# CPU.net
KiCad netlist of a schematic drawn in Altium Designer
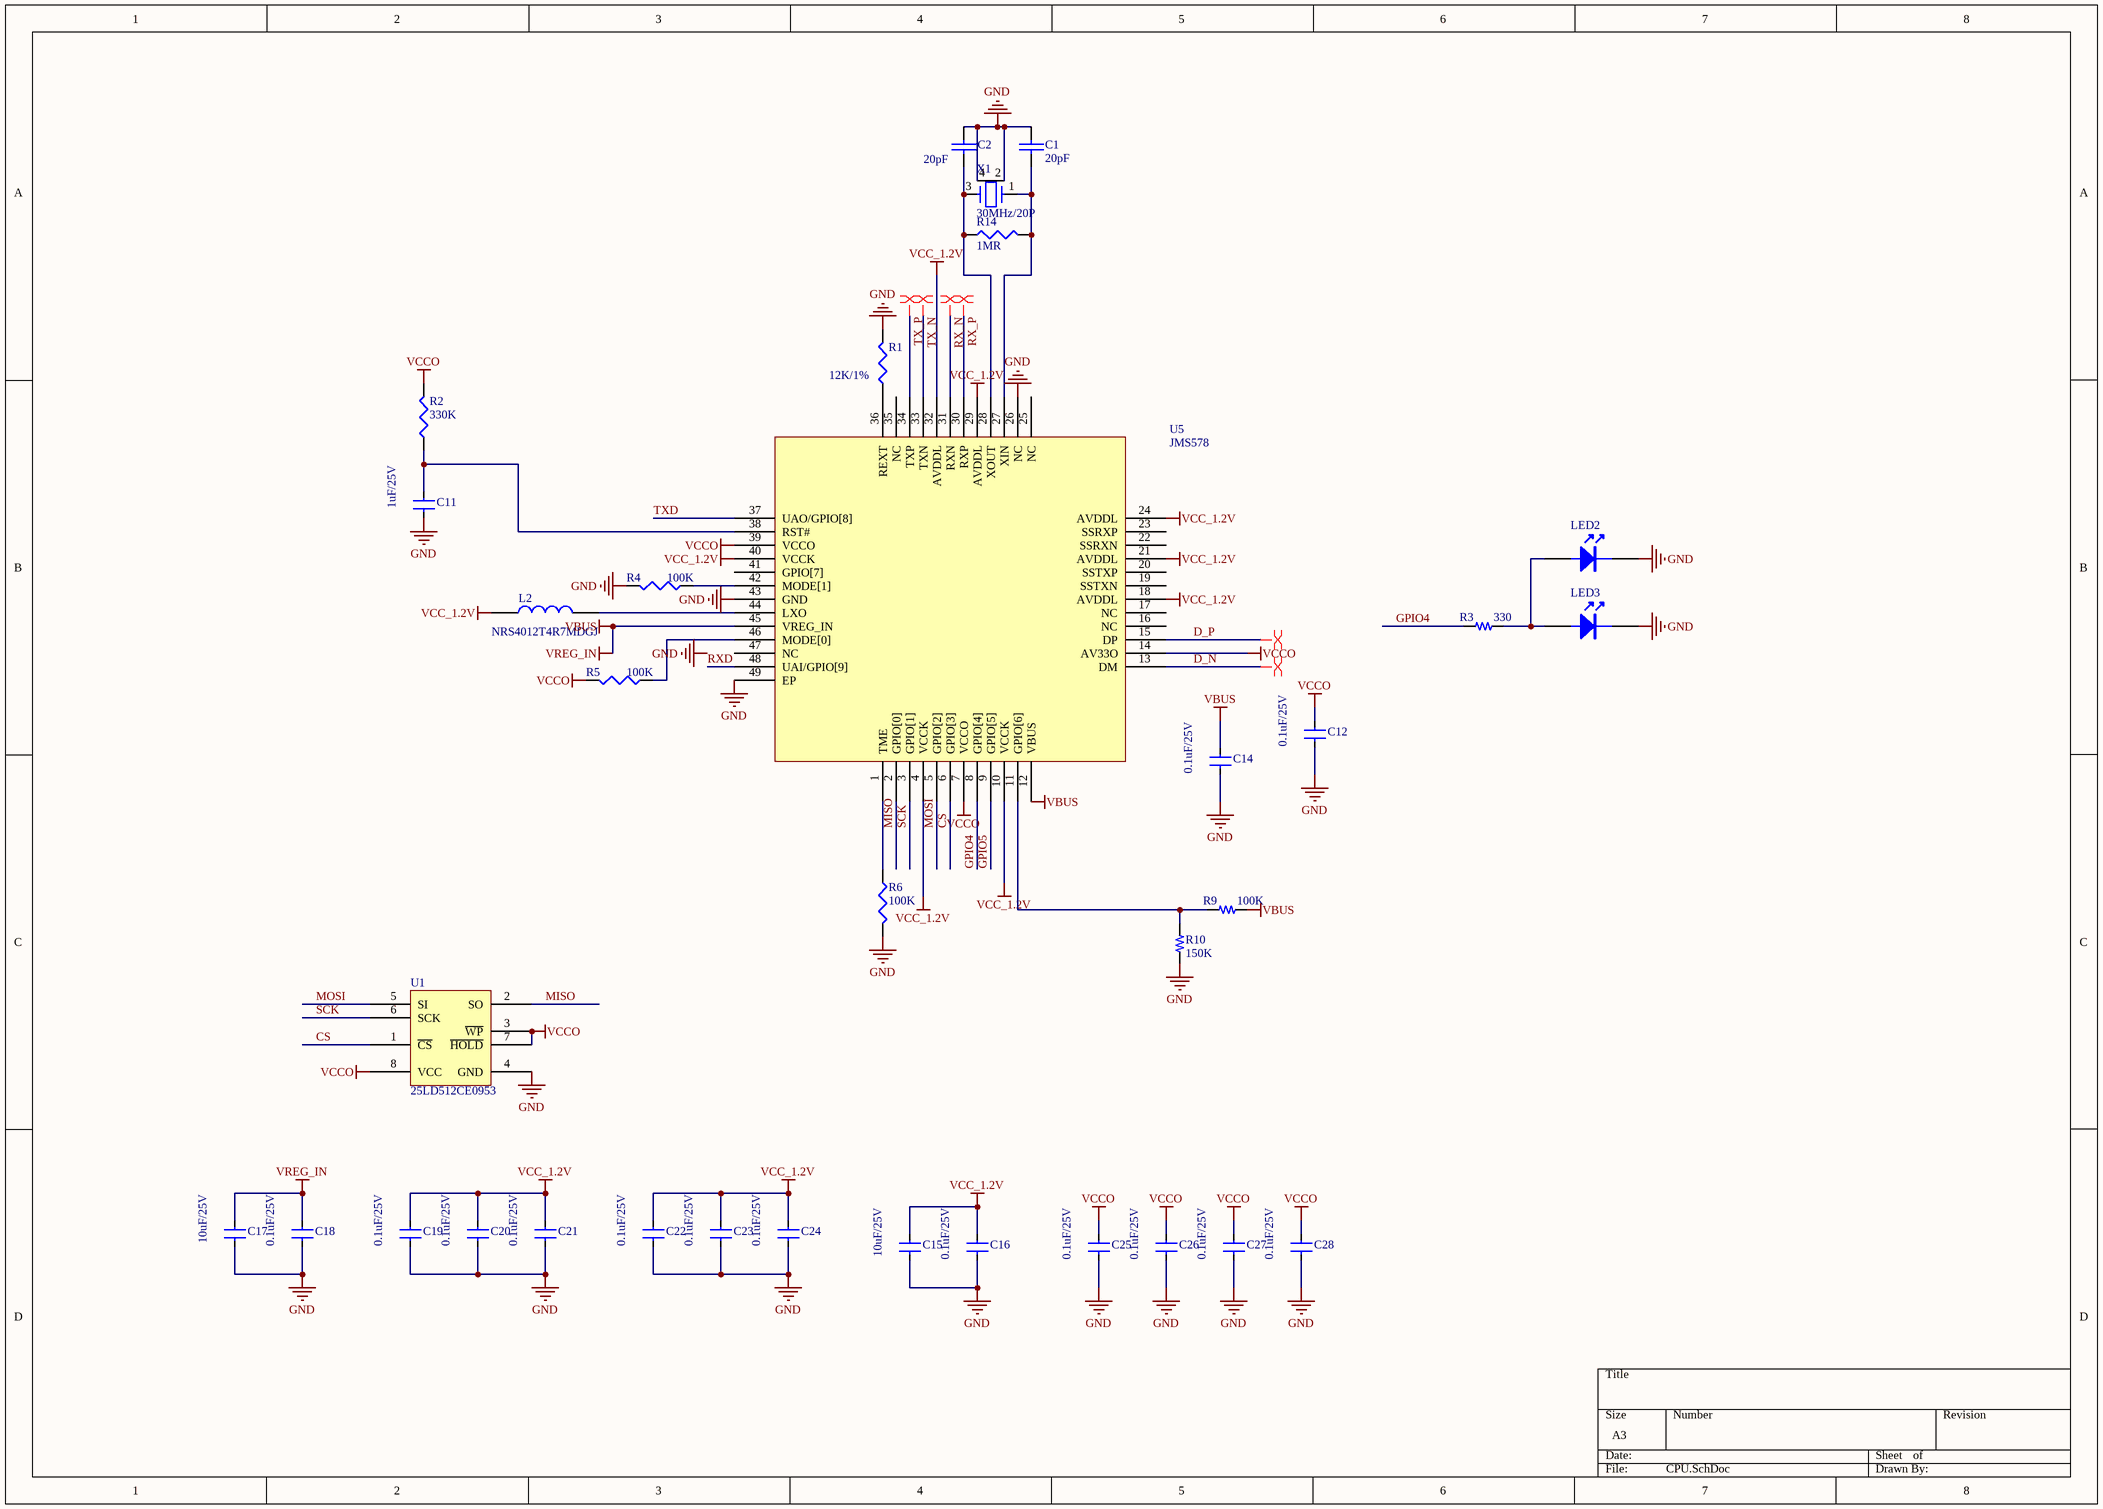
[diagram p0: CPU.SchDoc]

(export (version "E")
  (design (tool "Eeschema 10.0.6"))
  (components
    (comp (ref "C1")
      (value "20pF")
      (footprint "0603c")
      (description "Capacitor")
      (libsource (lib "SM") (part "CAP"))
    )
    (comp (ref "C2")
      (value "20pF")
      (footprint "0603C")
      (description "Capacitor")
      (libsource (lib "SM") (part "CAP"))
    )
    (comp (ref "C11")
      (value "1uF/25V")
      (footprint "0603C")
      (description "CCX85-103")
      (libsource (lib "无极性电容") (part "0.01UF"))
    )
    (comp (ref "C12")
      (value "0.1uF/25V")
      (footprint "0603C")
      (description "CCX85-103")
      (libsource (lib "无极性电容") (part "0.01UF"))
    )
    (comp (ref "C14")
      (value "0.1uF/25V")
      (footprint "0603C")
      (description "CCX85-103")
      (libsource (lib "无极性电容") (part "0.01UF"))
    )
    (comp (ref "C15")
      (value "10uF/25V")
      (footprint "0603C")
      (description "CCX85-103")
      (libsource (lib "无极性电容") (part "0.01UF"))
    )
    (comp (ref "C16")
      (value "0.1uF/25V")
      (footprint "0603C")
      (description "CCX85-103")
      (libsource (lib "无极性电容") (part "0.01UF"))
    )
    (comp (ref "C17")
      (value "10uF/25V")
      (footprint "0603C")
      (description "CCX85-103")
      (libsource (lib "无极性电容") (part "0.01UF"))
    )
    (comp (ref "C18")
      (value "0.1uF/25V")
      (footprint "0603C")
      (description "CCX85-103")
      (libsource (lib "无极性电容") (part "0.01UF"))
    )
    (comp (ref "C19")
      (value "0.1uF/25V")
      (footprint "0603C")
      (description "CCX85-103")
      (libsource (lib "无极性电容") (part "0.01UF"))
    )
    (comp (ref "C20")
      (value "0.1uF/25V")
      (footprint "0603C")
      (description "CCX85-103")
      (libsource (lib "无极性电容") (part "0.01UF"))
    )
    (comp (ref "C21")
      (value "0.1uF/25V")
      (footprint "0603C")
      (description "CCX85-103")
      (libsource (lib "无极性电容") (part "0.01UF"))
    )
    (comp (ref "C22")
      (value "0.1uF/25V")
      (footprint "0603C")
      (description "CCX85-103")
      (libsource (lib "无极性电容") (part "0.01UF"))
    )
    (comp (ref "C23")
      (value "0.1uF/25V")
      (footprint "0603C")
      (description "CCX85-103")
      (libsource (lib "无极性电容") (part "0.01UF"))
    )
    (comp (ref "C24")
      (value "0.1uF/25V")
      (footprint "0603C")
      (description "CCX85-103")
      (libsource (lib "无极性电容") (part "0.01UF"))
    )
    (comp (ref "C25")
      (value "0.1uF/25V")
      (footprint "0603C")
      (description "CCX85-103")
      (libsource (lib "无极性电容") (part "0.01UF"))
    )
    (comp (ref "C26")
      (value "0.1uF/25V")
      (footprint "0603C")
      (description "CCX85-103")
      (libsource (lib "无极性电容") (part "0.01UF"))
    )
    (comp (ref "C27")
      (value "0.1uF/25V")
      (footprint "0603C")
      (description "CCX85-103")
      (libsource (lib "无极性电容") (part "0.01UF"))
    )
    (comp (ref "C28")
      (value "0.1uF/25V")
      (footprint "0603C")
      (description "CCX85-103")
      (libsource (lib "无极性电容") (part "0.01UF"))
    )
    (comp (ref "L2")
      (value "NRS4012T4R7MDGJ")
      (footprint "NRS4012T4R7MDGJ")
      (libsource (lib "*") (part "INDUCTOR"))
    )
    (comp (ref "LED2") (value "~") (footprint "0603LED") (libsource (lib "*") (part "LED")))
    (comp (ref "LED3") (value "~") (footprint "0603LED") (libsource (lib "*") (part "LED")))
    (comp (ref "R1")
      (value "12K/1%")
      (footprint "0603R")
      (description "Resistor")
      (fields (field (name "PUBLISHER") "Altium Limited"))
      (libsource (lib "SM") (part "Res3"))
    )
    (comp (ref "R2")
      (value "330K")
      (footprint "0603R")
      (description "Resistor")
      (fields (field (name "PUBLISHER") "Altium Limited"))
      (libsource (lib "SM") (part "Res3"))
    )
    (comp (ref "R3") (value "330") (footprint "0603R") (description "R") (libsource (lib "JRJ_1") (part "R")))
    (comp (ref "R4")
      (value "100K")
      (footprint "0603R")
      (description "Resistor")
      (fields (field (name "PUBLISHER") "Altium Limited"))
      (libsource (lib "SM") (part "Res3"))
    )
    (comp (ref "R5")
      (value "100K")
      (footprint "0603R")
      (description "Resistor")
      (fields (field (name "PUBLISHER") "Altium Limited"))
      (libsource (lib "SM") (part "Res3"))
    )
    (comp (ref "R6")
      (value "100K")
      (footprint "0603R")
      (description "Resistor")
      (fields (field (name "PUBLISHER") "Altium Limited"))
      (libsource (lib "SM") (part "Res3"))
    )
    (comp (ref "R9")
      (value "100K")
      (footprint "0603R")
      (description "R")
      (libsource (lib "JRJ_1") (part "R"))
    )
    (comp (ref "R10")
      (value "150K")
      (footprint "0603R")
      (description "R")
      (libsource (lib "JRJ_1") (part "R"))
    )
    (comp (ref "R14")
      (value "1MR")
      (footprint "0603R")
      (description "Resistor")
      (fields (field (name "PUBLISHER") "Altium Limited"))
      (libsource (lib "SM") (part "Res3"))
    )
    (comp (ref "U1")
      (value "25LD512CE0953")
      (footprint "SO-8")
      (libsource (lib "Schlib_20110825") (part "M25P40-VMN6"))
    )
    (comp (ref "U5") (value "JMS578") (footprint "QFN400P600-8N") (libsource (lib "stm32") (part "JMS578")))
    (comp (ref "X1")
      (value "30MHz/20P")
      (footprint "XTAL4TN_3225")
      (libsource (lib "JRJ") (part "CRYSTAL_2"))
    )
  )
  (nets
    (net (code "1") (name "/CS") (class "Default")
      (node (ref "U1") (pin "1") (pinfunction "~{CS}_1") (pintype "passive"))
      (node (ref "U5") (pin "6") (pinfunction "GPIO[3]_6") (pintype "passive"))
    )
    (net (code "2") (name "/D_N") (class "Default")
      (node (ref "U5") (pin "13") (pinfunction "DM_13") (pintype "passive"))
    )
    (net (code "3") (name "/D_P") (class "Default")
      (node (ref "U5") (pin "15") (pinfunction "DP_15") (pintype "passive"))
    )
    (net (code "4") (name "/GPIO4") (class "Default")
      (node (ref "R3") (pin "1") (pintype "passive"))
      (node (ref "U5") (pin "8") (pinfunction "GPIO[4]_8") (pintype "passive"))
    )
    (net (code "5") (name "/GPIO5") (class "Default")
      (node (ref "U5") (pin "9") (pinfunction "GPIO[5]_9") (pintype "passive"))
    )
    (net (code "6") (name "/MISO") (class "Default")
      (node (ref "U1") (pin "2") (pinfunction "SO_2") (pintype "passive"))
      (node (ref "U5") (pin "2") (pinfunction "GPIO[0]_2") (pintype "passive"))
    )
    (net (code "7") (name "/MOSI") (class "Default")
      (node (ref "U1") (pin "5") (pinfunction "SI_5") (pintype "passive"))
      (node (ref "U5") (pin "5") (pinfunction "GPIO[2]_5") (pintype "passive"))
    )
    (net (code "8") (name "/RXD") (class "Default")
      (node (ref "U5") (pin "48") (pinfunction "UAI/GPIO[9]_48") (pintype "passive"))
    )
    (net (code "9") (name "/RX_N") (class "Default")
      (node (ref "U5") (pin "31") (pinfunction "RXN_31") (pintype "passive"))
    )
    (net (code "10") (name "/RX_P") (class "Default")
      (node (ref "U5") (pin "30") (pinfunction "RXP_30") (pintype "passive"))
    )
    (net (code "11") (name "/SCK") (class "Default")
      (node (ref "U1") (pin "6") (pinfunction "SCK_6") (pintype "passive"))
      (node (ref "U5") (pin "3") (pinfunction "GPIO[1]_3") (pintype "passive"))
    )
    (net (code "12") (name "/TXD") (class "Default")
      (node (ref "U5") (pin "37") (pinfunction "UAO/GPIO[8]_37") (pintype "passive"))
    )
    (net (code "13") (name "/TX_N") (class "Default")
      (node (ref "U5") (pin "33") (pinfunction "TXN_33") (pintype "passive"))
    )
    (net (code "14") (name "/TX_P") (class "Default")
      (node (ref "U5") (pin "34") (pinfunction "TXP_34") (pintype "passive"))
    )
    (net (code "15") (name "GND") (class "Default")
      (node (ref "C1") (pin "1") (pinfunction "1_1") (pintype "passive"))
      (node (ref "C11") (pin "2") (pinfunction "2_2") (pintype "passive"))
      (node (ref "C12") (pin "2") (pinfunction "2_2") (pintype "passive"))
      (node (ref "C14") (pin "2") (pinfunction "2_2") (pintype "passive"))
      (node (ref "C15") (pin "2") (pinfunction "2_2") (pintype "passive"))
      (node (ref "C16") (pin "2") (pinfunction "2_2") (pintype "passive"))
      (node (ref "C17") (pin "2") (pinfunction "2_2") (pintype "passive"))
      (node (ref "C18") (pin "2") (pinfunction "2_2") (pintype "passive"))
      (node (ref "C19") (pin "2") (pinfunction "2_2") (pintype "passive"))
      (node (ref "C2") (pin "1") (pinfunction "1_1") (pintype "passive"))
      (node (ref "C20") (pin "2") (pinfunction "2_2") (pintype "passive"))
      (node (ref "C21") (pin "2") (pinfunction "2_2") (pintype "passive"))
      (node (ref "C22") (pin "2") (pinfunction "2_2") (pintype "passive"))
      (node (ref "C23") (pin "2") (pinfunction "2_2") (pintype "passive"))
      (node (ref "C24") (pin "2") (pinfunction "2_2") (pintype "passive"))
      (node (ref "C25") (pin "2") (pinfunction "2_2") (pintype "passive"))
      (node (ref "C26") (pin "2") (pinfunction "2_2") (pintype "passive"))
      (node (ref "C27") (pin "2") (pinfunction "2_2") (pintype "passive"))
      (node (ref "C28") (pin "2") (pinfunction "2_2") (pintype "passive"))
      (node (ref "LED2") (pin "2") (pinfunction "2_2") (pintype "passive"))
      (node (ref "LED3") (pin "2") (pinfunction "2_2") (pintype "passive"))
      (node (ref "R1") (pin "2") (pinfunction "2_2") (pintype "passive"))
      (node (ref "R10") (pin "1") (pintype "passive"))
      (node (ref "R4") (pin "2") (pinfunction "2_2") (pintype "passive"))
      (node (ref "R6") (pin "2") (pinfunction "2_2") (pintype "passive"))
      (node (ref "U1") (pin "4") (pinfunction "GND_4") (pintype "passive"))
      (node (ref "U5") (pin "26") (pinfunction "NC_26") (pintype "passive"))
      (node (ref "U5") (pin "43") (pinfunction "GND_43") (pintype "passive"))
      (node (ref "U5") (pin "49") (pinfunction "EP_49") (pintype "passive"))
      (node (ref "X1") (pin "2") (pinfunction "GND_2") (pintype "passive"))
      (node (ref "X1") (pin "4") (pinfunction "GND_4") (pintype "passive"))
    )
    (net (code "16") (name "Net-(LED2-Pad1)") (class "Default")
      (node (ref "LED2") (pin "1") (pinfunction "1_1") (pintype "passive"))
      (node (ref "LED3") (pin "1") (pinfunction "1_1") (pintype "passive"))
      (node (ref "R3") (pin "2") (pintype "passive"))
    )
    (net (code "17") (name "Net-(U5-GPIO[6])") (class "Default")
      (node (ref "R10") (pin "2") (pintype "passive"))
      (node (ref "R9") (pin "1") (pintype "passive"))
      (node (ref "U5") (pin "11") (pinfunction "GPIO[6]_11") (pintype "passive"))
    )
    (net (code "18") (name "Net-(U5-LXO)") (class "Default")
      (node (ref "L2") (pin "2") (pinfunction "2_2") (pintype "passive"))
      (node (ref "U5") (pin "44") (pinfunction "LXO_44") (pintype "passive"))
    )
    (net (code "19") (name "Net-(U5-MODE[0])") (class "Default")
      (node (ref "R5") (pin "1") (pinfunction "1_1") (pintype "passive"))
      (node (ref "U5") (pin "46") (pinfunction "MODE[0]_46") (pintype "passive"))
    )
    (net (code "20") (name "Net-(U5-MODE[1])") (class "Default")
      (node (ref "R4") (pin "1") (pinfunction "1_1") (pintype "passive"))
      (node (ref "U5") (pin "42") (pinfunction "MODE[1]_42") (pintype "passive"))
    )
    (net (code "21") (name "Net-(U5-REXT)") (class "Default")
      (node (ref "R1") (pin "1") (pinfunction "1_1") (pintype "passive"))
      (node (ref "U5") (pin "36") (pinfunction "REXT_36") (pintype "passive"))
    )
    (net (code "22") (name "Net-(U5-RST#)") (class "Default")
      (node (ref "C11") (pin "1") (pinfunction "1_1") (pintype "passive"))
      (node (ref "R2") (pin "1") (pinfunction "1_1") (pintype "passive"))
      (node (ref "U5") (pin "38") (pinfunction "RST#_38") (pintype "passive"))
    )
    (net (code "23") (name "Net-(U5-TME)") (class "Default")
      (node (ref "R6") (pin "1") (pinfunction "1_1") (pintype "passive"))
      (node (ref "U5") (pin "1") (pinfunction "TME_1") (pintype "passive"))
    )
    (net (code "24") (name "Net-(U5-XIN)") (class "Default")
      (node (ref "C1") (pin "2") (pinfunction "2_2") (pintype "passive"))
      (node (ref "R14") (pin "2") (pinfunction "2_2") (pintype "passive"))
      (node (ref "U5") (pin "27") (pinfunction "XIN_27") (pintype "passive"))
      (node (ref "X1") (pin "1") (pinfunction "X1_1") (pintype "passive"))
    )
    (net (code "25") (name "Net-(U5-XOUT)") (class "Default")
      (node (ref "C2") (pin "2") (pinfunction "2_2") (pintype "passive"))
      (node (ref "R14") (pin "1") (pinfunction "1_1") (pintype "passive"))
      (node (ref "U5") (pin "28") (pinfunction "XOUT_28") (pintype "passive"))
      (node (ref "X1") (pin "3") (pinfunction "X2_3") (pintype "passive"))
    )
    (net (code "26") (name "VBUS") (class "Default")
      (node (ref "C14") (pin "1") (pinfunction "1_1") (pintype "passive"))
      (node (ref "C17") (pin "1") (pinfunction "1_1") (pintype "passive"))
      (node (ref "C18") (pin "1") (pinfunction "1_1") (pintype "passive"))
      (node (ref "R9") (pin "2") (pintype "passive"))
      (node (ref "U5") (pin "12") (pinfunction "VBUS_12") (pintype "passive"))
      (node (ref "U5") (pin "45") (pinfunction "VREG_IN_45") (pintype "passive"))
    )
    (net (code "27") (name "VCCO") (class "Default")
      (node (ref "C12") (pin "1") (pinfunction "1_1") (pintype "passive"))
      (node (ref "C25") (pin "1") (pinfunction "1_1") (pintype "passive"))
      (node (ref "C26") (pin "1") (pinfunction "1_1") (pintype "passive"))
      (node (ref "C27") (pin "1") (pinfunction "1_1") (pintype "passive"))
      (node (ref "C28") (pin "1") (pinfunction "1_1") (pintype "passive"))
      (node (ref "R2") (pin "2") (pinfunction "2_2") (pintype "passive"))
      (node (ref "R5") (pin "2") (pinfunction "2_2") (pintype "passive"))
      (node (ref "U1") (pin "3") (pinfunction "~{WP}_3") (pintype "passive"))
      (node (ref "U1") (pin "7") (pinfunction "~{HOLD}_7") (pintype "passive"))
      (node (ref "U1") (pin "8") (pinfunction "VCC_8") (pintype "passive"))
      (node (ref "U5") (pin "14") (pinfunction "AV33O_14") (pintype "passive"))
      (node (ref "U5") (pin "39") (pinfunction "VCCO_39") (pintype "passive"))
      (node (ref "U5") (pin "7") (pinfunction "VCCO_7") (pintype "passive"))
    )
    (net (code "28") (name "VCC_1.2V") (class "Default")
      (node (ref "C15") (pin "1") (pinfunction "1_1") (pintype "passive"))
      (node (ref "C16") (pin "1") (pinfunction "1_1") (pintype "passive"))
      (node (ref "C19") (pin "1") (pinfunction "1_1") (pintype "passive"))
      (node (ref "C20") (pin "1") (pinfunction "1_1") (pintype "passive"))
      (node (ref "C21") (pin "1") (pinfunction "1_1") (pintype "passive"))
      (node (ref "C22") (pin "1") (pinfunction "1_1") (pintype "passive"))
      (node (ref "C23") (pin "1") (pinfunction "1_1") (pintype "passive"))
      (node (ref "C24") (pin "1") (pinfunction "1_1") (pintype "passive"))
      (node (ref "L2") (pin "1") (pinfunction "1_1") (pintype "passive"))
      (node (ref "U5") (pin "10") (pinfunction "VCCK_10") (pintype "passive"))
      (node (ref "U5") (pin "18") (pinfunction "AVDDL_18") (pintype "passive"))
      (node (ref "U5") (pin "21") (pinfunction "AVDDL_21") (pintype "passive"))
      (node (ref "U5") (pin "24") (pinfunction "AVDDL_24") (pintype "passive"))
      (node (ref "U5") (pin "29") (pinfunction "AVDDL_29") (pintype "passive"))
      (node (ref "U5") (pin "32") (pinfunction "AVDDL_32") (pintype "passive"))
      (node (ref "U5") (pin "4") (pinfunction "VCCK_4") (pintype "passive"))
      (node (ref "U5") (pin "40") (pinfunction "VCCK_40") (pintype "passive"))
    )
    (net (code "29") (name "unconnected-(U5-GPIO[7]-Pad41)") (class "Default")
      (node (ref "U5") (pin "41") (pinfunction "GPIO[7]_41") (pintype "passive"))
    )
    (net (code "30") (name "unconnected-(U5-NC-Pad16)") (class "Default")
      (node (ref "U5") (pin "16") (pinfunction "NC_16") (pintype "passive"))
    )
    (net (code "31") (name "unconnected-(U5-NC-Pad17)") (class "Default")
      (node (ref "U5") (pin "17") (pinfunction "NC_17") (pintype "passive"))
    )
    (net (code "32") (name "unconnected-(U5-NC-Pad25)") (class "Default")
      (node (ref "U5") (pin "25") (pinfunction "NC_25") (pintype "passive"))
    )
    (net (code "33") (name "unconnected-(U5-NC-Pad35)") (class "Default")
      (node (ref "U5") (pin "35") (pinfunction "NC_35") (pintype "passive"))
    )
    (net (code "34") (name "unconnected-(U5-NC-Pad47)") (class "Default")
      (node (ref "U5") (pin "47") (pinfunction "NC_47") (pintype "passive"))
    )
    (net (code "35") (name "unconnected-(U5-SSRXN-Pad22)") (class "Default")
      (node (ref "U5") (pin "22") (pinfunction "SSRXN_22") (pintype "passive"))
    )
    (net (code "36") (name "unconnected-(U5-SSRXP-Pad23)") (class "Default")
      (node (ref "U5") (pin "23") (pinfunction "SSRXP_23") (pintype "passive"))
    )
    (net (code "37") (name "unconnected-(U5-SSTXN-Pad19)") (class "Default")
      (node (ref "U5") (pin "19") (pinfunction "SSTXN_19") (pintype "passive"))
    )
    (net (code "38") (name "unconnected-(U5-SSTXP-Pad20)") (class "Default")
      (node (ref "U5") (pin "20") (pinfunction "SSTXP_20") (pintype "passive"))
    )
  )
)
